# TOP.net
KiCad netlist of a schematic drawn in Altium Designer
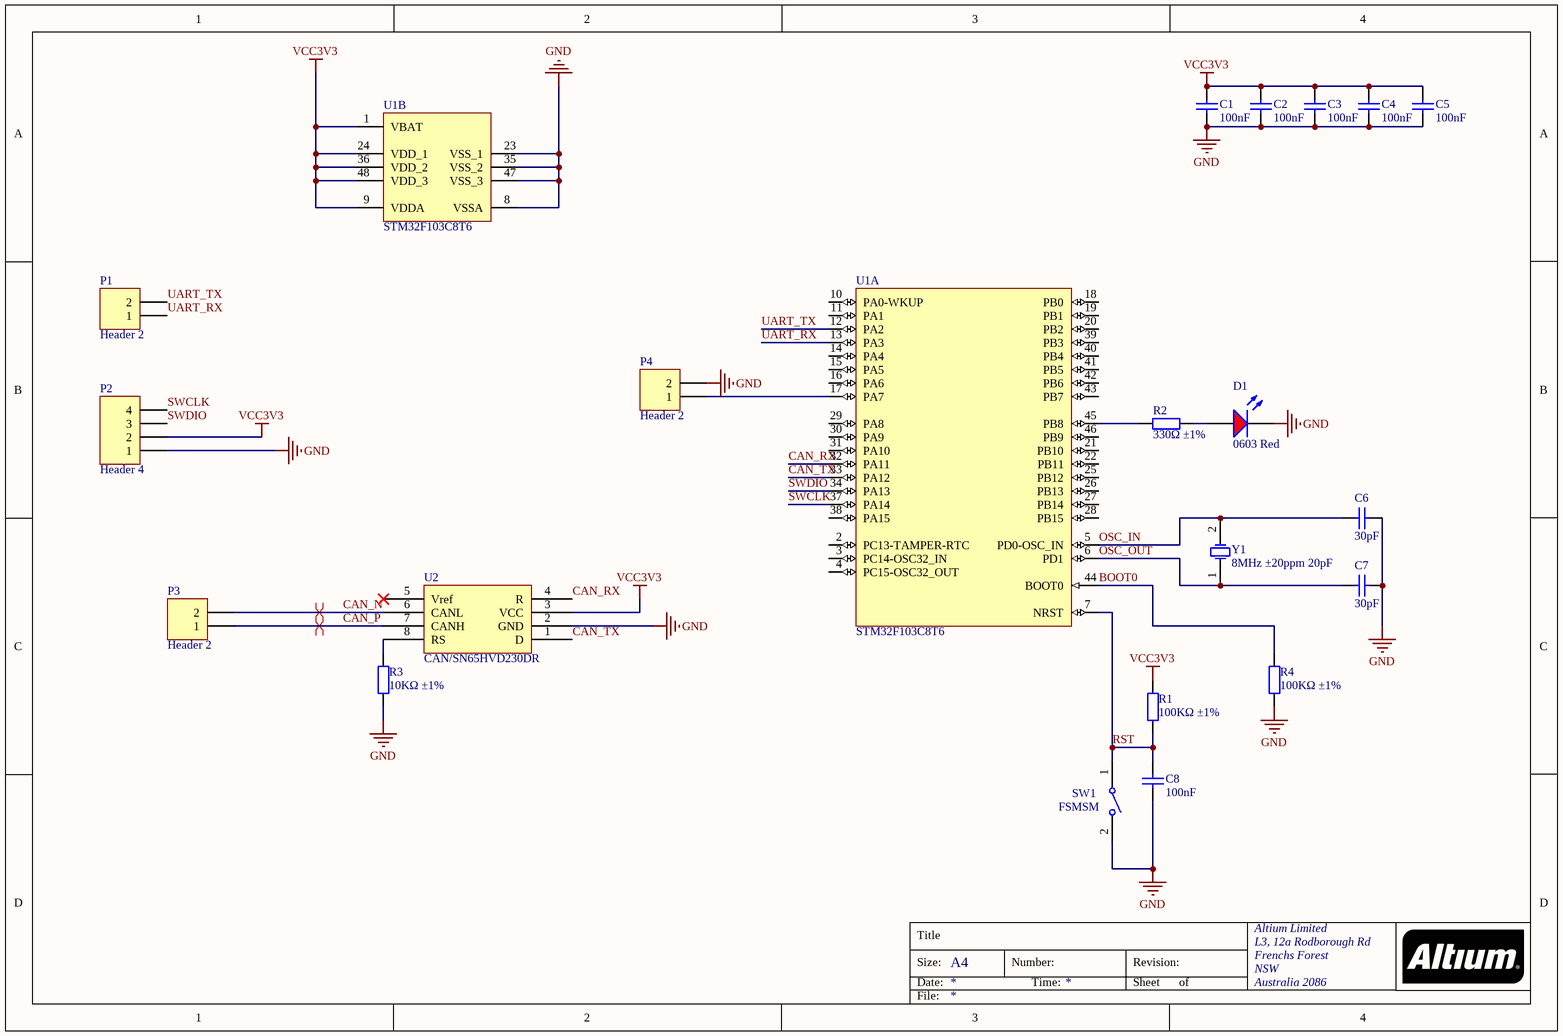
[diagram p0: TOP.SchDoc]

(export (version "E")
  (design (tool "Eeschema 10.0.6"))
  (components
    (comp (ref "C1")
      (value "100nF")
      (footprint "0402_C")
      (description "Chip capacitors")
      (fields
        (field (name "MANUFACTURER") "Samsung Electro-Mechanics")
        (field (name "PARTNUMBER") "CL05B104KO5NNNC")
      )
      (libsource (lib "Miscellaneous Devices LC") (part "0402 100nF (104) 10% 16V"))
    )
    (comp (ref "C2")
      (value "100nF")
      (footprint "0402_C")
      (description "Chip capacitors")
      (fields
        (field (name "MANUFACTURER") "Samsung Electro-Mechanics")
        (field (name "PARTNUMBER") "CL05B104KO5NNNC")
      )
      (libsource (lib "Miscellaneous Devices LC") (part "0402 100nF (104) 10% 16V"))
    )
    (comp (ref "C3")
      (value "100nF")
      (footprint "0402_C")
      (description "Chip capacitors")
      (fields
        (field (name "MANUFACTURER") "Samsung Electro-Mechanics")
        (field (name "PARTNUMBER") "CL05B104KO5NNNC")
      )
      (libsource (lib "Miscellaneous Devices LC") (part "0402 100nF (104) 10% 16V"))
    )
    (comp (ref "C4")
      (value "100nF")
      (footprint "0402_C")
      (description "Chip capacitors")
      (fields
        (field (name "MANUFACTURER") "Samsung Electro-Mechanics")
        (field (name "PARTNUMBER") "CL05B104KO5NNNC")
      )
      (libsource (lib "Miscellaneous Devices LC") (part "0402 100nF (104) 10% 16V"))
    )
    (comp (ref "C5")
      (value "100nF")
      (footprint "0402_C")
      (description "Chip capacitors")
      (fields
        (field (name "MANUFACTURER") "Samsung Electro-Mechanics")
        (field (name "PARTNUMBER") "CL05B104KO5NNNC")
      )
      (libsource (lib "Miscellaneous Devices LC") (part "0402 100nF (104) 10% 16V"))
    )
    (comp (ref "C6")
      (value "30pF")
      (footprint "0402_C")
      (description "Chip capacitors")
      (fields
        (field (name "MANUFACTURER") "Guangdong Fenghua Advanced Tech")
        (field (name "PARTNUMBER") "0402CG300J500NT")
      )
      (libsource (lib "Miscellaneous Devices LC") (part "0402 30pF (300) 5% 50V"))
    )
    (comp (ref "C7")
      (value "30pF")
      (footprint "0402_C")
      (description "Chip capacitors")
      (fields
        (field (name "MANUFACTURER") "Guangdong Fenghua Advanced Tech")
        (field (name "PARTNUMBER") "0402CG300J500NT")
      )
      (libsource (lib "Miscellaneous Devices LC") (part "0402 30pF (300) 5% 50V"))
    )
    (comp (ref "C8")
      (value "100nF")
      (footprint "0402_C")
      (description "Chip capacitors")
      (fields
        (field (name "MANUFACTURER") "Samsung Electro-Mechanics")
        (field (name "PARTNUMBER") "CL05B104KO5NNNC")
      )
      (libsource (lib "Miscellaneous Devices LC") (part "0402 100nF (104) 10% 16V"))
    )
    (comp (ref "D1")
      (value "0603 Red")
      (footprint "0603_LED_S1")
      (description "LED")
      (libsource (lib "Miscellaneous Devices LC") (part "0603 LED Red"))
    )
    (comp (ref "P1")
      (value "Header 2")
      (footprint "HDR1X2")
      (description "Header, 2-Pin")
      (fields (field (name "PUBLISHER") "Altium Limited"))
      (libsource (lib "Miscellaneous Connectors") (part "Header 2"))
    )
    (comp (ref "P2")
      (value "Header 4")
      (footprint "HDR1X4")
      (description "Header, 4-Pin")
      (fields (field (name "PUBLISHER") "Altium Limited"))
      (libsource (lib "Miscellaneous Connectors") (part "Header 4"))
    )
    (comp (ref "P3")
      (value "Header 2")
      (footprint "HDR1X2")
      (description "Header, 2-Pin")
      (fields (field (name "PUBLISHER") "Altium Limited"))
      (libsource (lib "Miscellaneous Connectors") (part "Header 2"))
    )
    (comp (ref "P4")
      (value "Header 2")
      (footprint "HDR1X2")
      (description "Header, 2-Pin")
      (fields (field (name "PUBLISHER") "Altium Limited"))
      (libsource (lib "Miscellaneous Connectors") (part "Header 2"))
    )
    (comp (ref "R1")
      (value "100KΩ ±1%")
      (footprint "0402_R")
      (description "Chip resistor")
      (fields (field (name "MANUFACTURER") "Uniroyal Elec") (field (name "PARTNUMBER") "0402WGF1003TCE"))
      (libsource (lib "Miscellaneous Devices LC") (part "0402 100K (1003) 1%"))
    )
    (comp (ref "R2")
      (value "330Ω ±1%")
      (footprint "0402_R")
      (description "Chip resistor")
      (fields (field (name "MANUFACTURER") "Uniroyal Elec") (field (name "PARTNUMBER") "0402WGF3300TCE"))
      (libsource (lib "Miscellaneous Devices LC") (part "0402 330R (3300) 1%"))
    )
    (comp (ref "R3")
      (value "10KΩ ±1%")
      (footprint "0402_R")
      (description "Chip resistor")
      (fields (field (name "MANUFACTURER") "Uniroyal Elec") (field (name "PARTNUMBER") "0402WGF1002TCE"))
      (libsource (lib "Miscellaneous Devices LC") (part "0402 10K (1002) 1%"))
    )
    (comp (ref "R4")
      (value "100KΩ ±1%")
      (footprint "0402_R")
      (description "Chip resistor")
      (fields (field (name "MANUFACTURER") "Uniroyal Elec") (field (name "PARTNUMBER") "0402WGF1003TCE"))
      (libsource (lib "Miscellaneous Devices LC") (part "0402 100K (1003) 1%"))
    )
    (comp (ref "SW1")
      (value "FSMSM")
      (footprint "TECO-FSMSM-2_V")
      (description "FSMSM Push Button Switch, 50 mA, -35 to 85 degC, 2-Pin SMD, RoHS, Bulk")
      (fields (field (name "MANUFACTURER") "TE Connectivity"))
      (libsource (lib "Altium Content Vault") (part "SW-SPST-2_C"))
    )
    (comp (ref "U1")
      (value "STM32F103C8T6")
      (footprint "LQFP-48_7x7x05P")
      (description "ARM")
      (libsource (lib "Miscellaneous Devices LC") (part "STM32F103C8T6"))
    )
    (comp (ref "U2")
      (value "CAN/SN65HVD230DR")
      (footprint "SOIC-8_150mil")
      (description "CAN")
      (libsource (lib "Miscellaneous Devices LC") (part "CAN/SN65HVD230DR_[C12084]"))
    )
    (comp (ref "Y1")
      (value "8MHz ±20ppm 20pF")
      (footprint "SMD-5032_2P")
      (description "贴片晶振")
      (libsource (lib "Miscellaneous Devices LC") (part "SMD-5032_2P 8MHz 20ppm 20pF"))
    )
  )
  (nets
    (net (code "1") (name "/BOOT0") (class "Default")
      (node (ref "R4") (pin "2") (pinfunction "2_2") (pintype "passive"))
      (node (ref "U1") (pin "44") (pinfunction "BOOT0_44") (pintype "input"))
    )
    (net (code "2") (name "/CAN_N") (class "Default")
      (node (ref "P3") (pin "2") (pinfunction "2_2") (pintype "passive"))
      (node (ref "U2") (pin "6") (pinfunction "CANL_6") (pintype "passive"))
    )
    (net (code "3") (name "/CAN_P") (class "Default")
      (node (ref "P3") (pin "1") (pinfunction "1_1") (pintype "passive"))
      (node (ref "U2") (pin "7") (pinfunction "CANH_7") (pintype "passive"))
    )
    (net (code "4") (name "/CAN_RX") (class "Default")
      (node (ref "U1") (pin "32") (pinfunction "PA11_32") (pintype "bidirectional"))
      (node (ref "U2") (pin "4") (pinfunction "R_4") (pintype "passive"))
    )
    (net (code "5") (name "/CAN_TX") (class "Default")
      (node (ref "U1") (pin "33") (pinfunction "PA12_33") (pintype "bidirectional"))
      (node (ref "U2") (pin "1") (pinfunction "D_1") (pintype "passive"))
    )
    (net (code "6") (name "/OSC_IN") (class "Default")
      (node (ref "C6") (pin "1") (pinfunction "1_1") (pintype "passive"))
      (node (ref "U1") (pin "5") (pinfunction "PD0-OSC_IN_5") (pintype "bidirectional"))
      (node (ref "Y1") (pin "2") (pinfunction "OSC2_2") (pintype "passive"))
    )
    (net (code "7") (name "/OSC_OUT") (class "Default")
      (node (ref "C7") (pin "1") (pinfunction "1_1") (pintype "passive"))
      (node (ref "U1") (pin "6") (pinfunction "PD1_6") (pintype "bidirectional"))
      (node (ref "Y1") (pin "1") (pinfunction "OSC1_1") (pintype "passive"))
    )
    (net (code "8") (name "/RST") (class "Default")
      (node (ref "C8") (pin "2") (pinfunction "2_2") (pintype "passive"))
      (node (ref "R1") (pin "1") (pinfunction "1_1") (pintype "passive"))
      (node (ref "SW1") (pin "1") (pinfunction "1_1") (pintype "passive"))
      (node (ref "U1") (pin "7") (pinfunction "NRST_7") (pintype "bidirectional"))
    )
    (net (code "9") (name "/SWCLK") (class "Default")
      (node (ref "P2") (pin "4") (pinfunction "4_4") (pintype "passive"))
      (node (ref "U1") (pin "37") (pinfunction "PA14_37") (pintype "bidirectional"))
    )
    (net (code "10") (name "/SWDIO") (class "Default")
      (node (ref "P2") (pin "3") (pinfunction "3_3") (pintype "passive"))
      (node (ref "U1") (pin "34") (pinfunction "PA13_34") (pintype "bidirectional"))
    )
    (net (code "11") (name "/UART_RX") (class "Default")
      (node (ref "P1") (pin "1") (pinfunction "1_1") (pintype "passive"))
      (node (ref "U1") (pin "13") (pinfunction "PA3_13") (pintype "bidirectional"))
    )
    (net (code "12") (name "/UART_TX") (class "Default")
      (node (ref "P1") (pin "2") (pinfunction "2_2") (pintype "passive"))
      (node (ref "U1") (pin "12") (pinfunction "PA2_12") (pintype "bidirectional"))
    )
    (net (code "13") (name "GND") (class "Default")
      (node (ref "C1") (pin "1") (pinfunction "1_1") (pintype "passive"))
      (node (ref "C2") (pin "1") (pinfunction "1_1") (pintype "passive"))
      (node (ref "C3") (pin "1") (pinfunction "1_1") (pintype "passive"))
      (node (ref "C4") (pin "1") (pinfunction "1_1") (pintype "passive"))
      (node (ref "C5") (pin "1") (pinfunction "1_1") (pintype "passive"))
      (node (ref "C6") (pin "2") (pinfunction "2_2") (pintype "passive"))
      (node (ref "C7") (pin "2") (pinfunction "2_2") (pintype "passive"))
      (node (ref "C8") (pin "1") (pinfunction "1_1") (pintype "passive"))
      (node (ref "D1") (pin "K") (pinfunction "K_K") (pintype "passive"))
      (node (ref "P2") (pin "1") (pinfunction "1_1") (pintype "passive"))
      (node (ref "P4") (pin "2") (pinfunction "2_2") (pintype "passive"))
      (node (ref "R3") (pin "1") (pinfunction "1_1") (pintype "passive"))
      (node (ref "R4") (pin "1") (pinfunction "1_1") (pintype "passive"))
      (node (ref "SW1") (pin "2") (pinfunction "2_2") (pintype "passive"))
      (node (ref "U1") (pin "23") (pinfunction "VSS_1_23") (pintype "power_in"))
      (node (ref "U1") (pin "35") (pinfunction "VSS_2_35") (pintype "power_in"))
      (node (ref "U1") (pin "47") (pinfunction "VSS_3_47") (pintype "power_in"))
      (node (ref "U1") (pin "8") (pinfunction "VSSA_8") (pintype "power_in"))
      (node (ref "U2") (pin "2") (pinfunction "GND_2") (pintype "passive"))
    )
    (net (code "14") (name "Net-(D1-PadA)") (class "Default")
      (node (ref "D1") (pin "A") (pinfunction "A_A") (pintype "passive"))
      (node (ref "R2") (pin "2") (pinfunction "2_2") (pintype "passive"))
    )
    (net (code "15") (name "Net-(U1A-PA7)") (class "Default")
      (node (ref "P4") (pin "1") (pinfunction "1_1") (pintype "passive"))
      (node (ref "U1") (pin "17") (pinfunction "PA7_17") (pintype "bidirectional"))
    )
    (net (code "16") (name "Net-(U1A-PB8)") (class "Default")
      (node (ref "R2") (pin "1") (pinfunction "1_1") (pintype "passive"))
      (node (ref "U1") (pin "45") (pinfunction "PB8_45") (pintype "bidirectional"))
    )
    (net (code "17") (name "Net-(U2-RS)") (class "Default")
      (node (ref "R3") (pin "2") (pinfunction "2_2") (pintype "passive"))
      (node (ref "U2") (pin "8") (pinfunction "RS_8") (pintype "passive"))
    )
    (net (code "18") (name "VCC3V3") (class "Default")
      (node (ref "C1") (pin "2") (pinfunction "2_2") (pintype "passive"))
      (node (ref "C2") (pin "2") (pinfunction "2_2") (pintype "passive"))
      (node (ref "C3") (pin "2") (pinfunction "2_2") (pintype "passive"))
      (node (ref "C4") (pin "2") (pinfunction "2_2") (pintype "passive"))
      (node (ref "C5") (pin "2") (pinfunction "2_2") (pintype "passive"))
      (node (ref "P2") (pin "2") (pinfunction "2_2") (pintype "passive"))
      (node (ref "R1") (pin "2") (pinfunction "2_2") (pintype "passive"))
      (node (ref "U1") (pin "1") (pinfunction "VBAT_1") (pintype "power_in"))
      (node (ref "U1") (pin "24") (pinfunction "VDD_1_24") (pintype "power_in"))
      (node (ref "U1") (pin "36") (pinfunction "VDD_2_36") (pintype "power_in"))
      (node (ref "U1") (pin "48") (pinfunction "VDD_3_48") (pintype "power_in"))
      (node (ref "U1") (pin "9") (pinfunction "VDDA_9") (pintype "power_in"))
      (node (ref "U2") (pin "3") (pinfunction "VCC_3") (pintype "passive"))
    )
    (net (code "19") (name "unconnected-(U1A-PA0-WKUP-Pad10)") (class "Default")
      (node (ref "U1") (pin "10") (pinfunction "PA0-WKUP_10") (pintype "bidirectional"))
    )
    (net (code "20") (name "unconnected-(U1A-PA1-Pad11)") (class "Default")
      (node (ref "U1") (pin "11") (pinfunction "PA1_11") (pintype "bidirectional"))
    )
    (net (code "21") (name "unconnected-(U1A-PA4-Pad14)") (class "Default")
      (node (ref "U1") (pin "14") (pinfunction "PA4_14") (pintype "bidirectional"))
    )
    (net (code "22") (name "unconnected-(U1A-PA5-Pad15)") (class "Default")
      (node (ref "U1") (pin "15") (pinfunction "PA5_15") (pintype "bidirectional"))
    )
    (net (code "23") (name "unconnected-(U1A-PA6-Pad16)") (class "Default")
      (node (ref "U1") (pin "16") (pinfunction "PA6_16") (pintype "bidirectional"))
    )
    (net (code "24") (name "unconnected-(U1A-PA8-Pad29)") (class "Default")
      (node (ref "U1") (pin "29") (pinfunction "PA8_29") (pintype "bidirectional"))
    )
    (net (code "25") (name "unconnected-(U1A-PA9-Pad30)") (class "Default")
      (node (ref "U1") (pin "30") (pinfunction "PA9_30") (pintype "bidirectional"))
    )
    (net (code "26") (name "unconnected-(U1A-PA10-Pad31)") (class "Default")
      (node (ref "U1") (pin "31") (pinfunction "PA10_31") (pintype "bidirectional"))
    )
    (net (code "27") (name "unconnected-(U1A-PA15-Pad38)") (class "Default")
      (node (ref "U1") (pin "38") (pinfunction "PA15_38") (pintype "bidirectional"))
    )
    (net (code "28") (name "unconnected-(U1A-PB0-Pad18)") (class "Default")
      (node (ref "U1") (pin "18") (pinfunction "PB0_18") (pintype "bidirectional"))
    )
    (net (code "29") (name "unconnected-(U1A-PB1-Pad19)") (class "Default")
      (node (ref "U1") (pin "19") (pinfunction "PB1_19") (pintype "bidirectional"))
    )
    (net (code "30") (name "unconnected-(U1A-PB2-Pad20)") (class "Default")
      (node (ref "U1") (pin "20") (pinfunction "PB2_20") (pintype "bidirectional"))
    )
    (net (code "31") (name "unconnected-(U1A-PB3-Pad39)") (class "Default")
      (node (ref "U1") (pin "39") (pinfunction "PB3_39") (pintype "bidirectional"))
    )
    (net (code "32") (name "unconnected-(U1A-PB4-Pad40)") (class "Default")
      (node (ref "U1") (pin "40") (pinfunction "PB4_40") (pintype "bidirectional"))
    )
    (net (code "33") (name "unconnected-(U1A-PB5-Pad41)") (class "Default")
      (node (ref "U1") (pin "41") (pinfunction "PB5_41") (pintype "bidirectional"))
    )
    (net (code "34") (name "unconnected-(U1A-PB6-Pad42)") (class "Default")
      (node (ref "U1") (pin "42") (pinfunction "PB6_42") (pintype "bidirectional"))
    )
    (net (code "35") (name "unconnected-(U1A-PB7-Pad43)") (class "Default")
      (node (ref "U1") (pin "43") (pinfunction "PB7_43") (pintype "bidirectional"))
    )
    (net (code "36") (name "unconnected-(U1A-PB9-Pad46)") (class "Default")
      (node (ref "U1") (pin "46") (pinfunction "PB9_46") (pintype "bidirectional"))
    )
    (net (code "37") (name "unconnected-(U1A-PB10-Pad21)") (class "Default")
      (node (ref "U1") (pin "21") (pinfunction "PB10_21") (pintype "bidirectional"))
    )
    (net (code "38") (name "unconnected-(U1A-PB11-Pad22)") (class "Default")
      (node (ref "U1") (pin "22") (pinfunction "PB11_22") (pintype "bidirectional"))
    )
    (net (code "39") (name "unconnected-(U1A-PB12-Pad25)") (class "Default")
      (node (ref "U1") (pin "25") (pinfunction "PB12_25") (pintype "bidirectional"))
    )
    (net (code "40") (name "unconnected-(U1A-PB13-Pad26)") (class "Default")
      (node (ref "U1") (pin "26") (pinfunction "PB13_26") (pintype "bidirectional"))
    )
    (net (code "41") (name "unconnected-(U1A-PB14-Pad27)") (class "Default")
      (node (ref "U1") (pin "27") (pinfunction "PB14_27") (pintype "bidirectional"))
    )
    (net (code "42") (name "unconnected-(U1A-PB15-Pad28)") (class "Default")
      (node (ref "U1") (pin "28") (pinfunction "PB15_28") (pintype "bidirectional"))
    )
    (net (code "43") (name "unconnected-(U1A-PC13-TAMPER-RTC-Pad2)") (class "Default")
      (node (ref "U1") (pin "2") (pinfunction "PC13-TAMPER-RTC_2") (pintype "bidirectional"))
    )
    (net (code "44") (name "unconnected-(U1A-PC14-OSC32_IN-Pad3)") (class "Default")
      (node (ref "U1") (pin "3") (pinfunction "PC14-OSC32_IN_3") (pintype "bidirectional"))
    )
    (net (code "45") (name "unconnected-(U1A-PC15-OSC32_OUT-Pad4)") (class "Default")
      (node (ref "U1") (pin "4") (pinfunction "PC15-OSC32_OUT_4") (pintype "bidirectional"))
    )
    (net (code "46") (name "unconnected-(U2-Vref-Pad5)") (class "Default")
      (node (ref "U2") (pin "5") (pinfunction "Vref_5") (pintype "passive+no_connect"))
    )
  )
)
